# LR_EVM78.net
KiCad netlist of a schematic drawn in Altium Designer
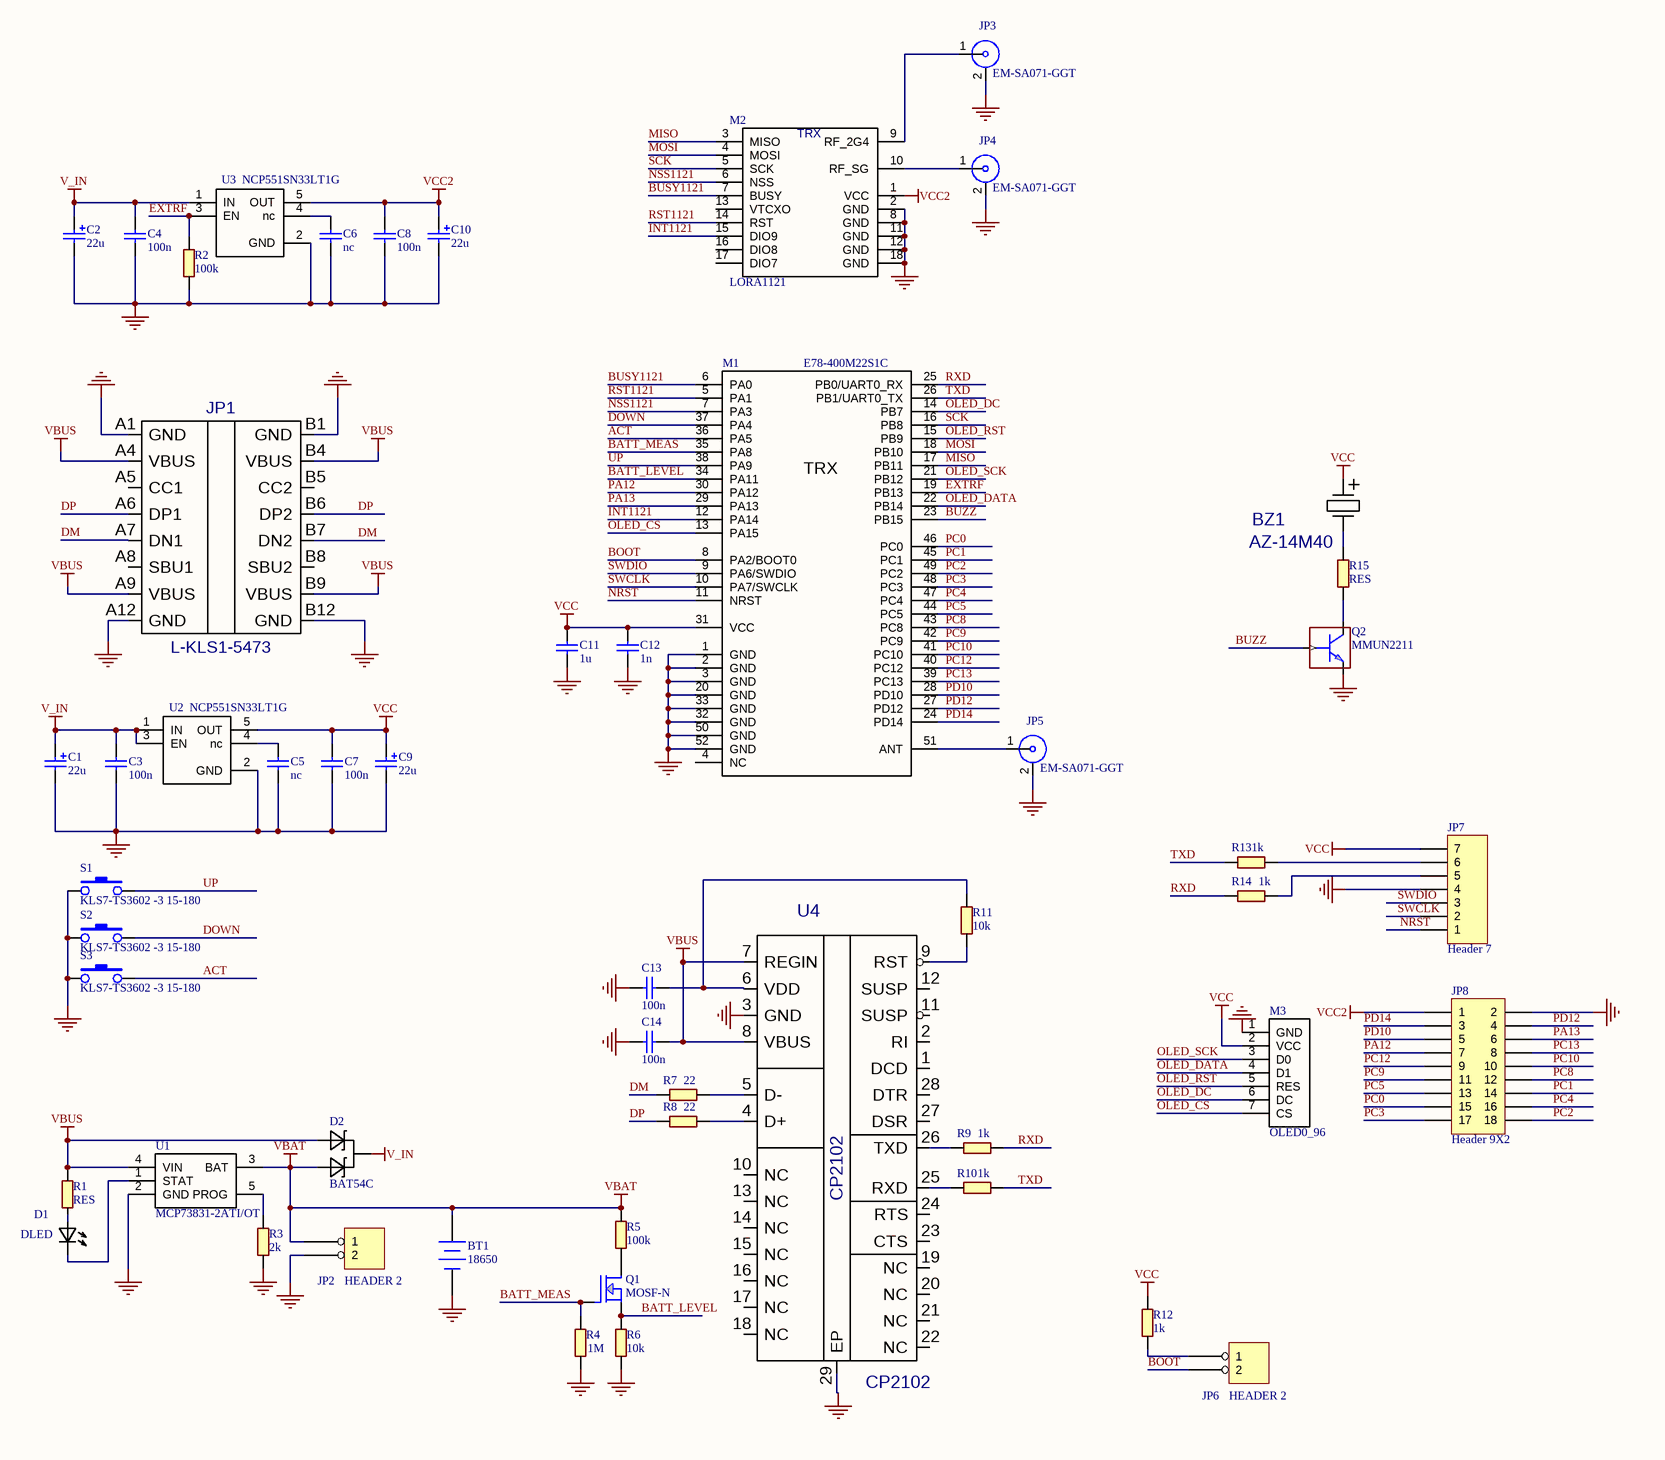
[diagram p0: LR_EVM78.SchDoc]

(export (version "E")
  (design (tool "Eeschema 10.0.6"))
  (components
    (comp (ref "BT1")
      (value "18650")
      (footprint "18650")
      (description "Multicell Battery")
      (fields (field (name "PUBLISHER") "Altium Limited"))
      (libsource (lib "zucker") (part "Battery"))
    )
    (comp (ref "BZ1")
      (value "AZ-14M40")
      (footprint "AZ-14M40")
      (libsource (lib "zucker") (part "BUZ-AZ-14M40"))
    )
    (comp (ref "C1")
      (value "22u")
      (footprint "C_TANTAL_A")
      (fields (field (name "VOLTAGE") "16V"))
      (libsource (lib "Passive") (part "CAPP"))
    )
    (comp (ref "C2")
      (value "22u")
      (footprint "C_TANTAL_A")
      (fields (field (name "VOLTAGE") "16V"))
      (libsource (lib "Passive") (part "CAPP"))
    )
    (comp (ref "C3")
      (value "100n")
      (footprint "C-0603")
      (fields (field (name "VOLTAGE") "50V"))
      (libsource (lib "Passive") (part "CAPN"))
    )
    (comp (ref "C4")
      (value "100n")
      (footprint "C-0603")
      (fields (field (name "VOLTAGE") "50V"))
      (libsource (lib "Passive") (part "CAPN"))
    )
    (comp (ref "C5")
      (value "nc")
      (footprint "C-0603")
      (fields (field (name "VOLTAGE") "50V"))
      (libsource (lib "Passive") (part "CAPN"))
    )
    (comp (ref "C6")
      (value "nc")
      (footprint "C-0603")
      (fields (field (name "VOLTAGE") "50V"))
      (libsource (lib "Passive") (part "CAPN"))
    )
    (comp (ref "C7")
      (value "100n")
      (footprint "C-0603")
      (fields (field (name "VOLTAGE") "50V"))
      (libsource (lib "Passive") (part "CAPN"))
    )
    (comp (ref "C8")
      (value "100n")
      (footprint "C-0603")
      (fields (field (name "VOLTAGE") "50V"))
      (libsource (lib "Passive") (part "CAPN"))
    )
    (comp (ref "C9")
      (value "22u")
      (footprint "C_TANTAL_A")
      (fields (field (name "VOLTAGE") "16V"))
      (libsource (lib "Passive") (part "CAPP"))
    )
    (comp (ref "C10")
      (value "22u")
      (footprint "C_TANTAL_A")
      (fields (field (name "VOLTAGE") "16V"))
      (libsource (lib "Passive") (part "CAPP"))
    )
    (comp (ref "C11")
      (value "1u")
      (footprint "C-0603")
      (fields (field (name "VOLTAGE") "50V"))
      (libsource (lib "Passive") (part "CAPN"))
    )
    (comp (ref "C12")
      (value "1n")
      (footprint "C-0603")
      (fields (field (name "VOLTAGE") "50V"))
      (libsource (lib "Passive") (part "CAPN"))
    )
    (comp (ref "C13")
      (value "100n")
      (footprint "C-0603")
      (fields (field (name "VOLTAGE") "50V"))
      (libsource (lib "Passive") (part "CAPN"))
    )
    (comp (ref "C14")
      (value "100n")
      (footprint "C-0603")
      (fields (field (name "VOLTAGE") "50V"))
      (libsource (lib "Passive") (part "CAPN"))
    )
    (comp (ref "D1") (value "DLED") (footprint "LED_3mm_RED") (libsource (lib "zucker") (part "DLED")))
    (comp (ref "D2") (value "BAT54C") (footprint "SOT-23") (libsource (lib "zucker") (part "BAT54C")))
    (comp (ref "JP1")
      (value "L-KLS1-5473")
      (footprint "L-KLS1-5473")
      (libsource (lib "connectors") (part "L-KLS1-5473"))
    )
    (comp (ref "JP2")
      (value "HEADER 2")
      (footprint "PLS1-2")
      (libsource (lib "Connectors") (part "HEADER 2"))
    )
    (comp (ref "JP3")
      (value "EM-SA071-GGT")
      (footprint "SMA_F_EDGE")
      (description "SMA Female R/A PCB Mount")
      (libsource (lib "Connectors") (part "SMA"))
    )
    (comp (ref "JP4")
      (value "EM-SA071-GGT")
      (footprint "SMA_F_EDGE")
      (description "SMA Female R/A PCB Mount")
      (libsource (lib "Connectors") (part "SMA"))
    )
    (comp (ref "JP5")
      (value "EM-SA071-GGT")
      (footprint "SMA_F_EDGE")
      (description "SMA Female R/A PCB Mount")
      (libsource (lib "Connectors") (part "SMA"))
    )
    (comp (ref "JP6")
      (value "HEADER 2")
      (footprint "PLS1-2")
      (libsource (lib "Connectors") (part "HEADER 2"))
    )
    (comp (ref "JP7")
      (value "Header 7")
      (footprint "PLS1-7R")
      (description "Header, 7-Pin")
      (fields (field (name "PUBLISHER") "Altium Limited"))
      (libsource (lib "Miscellaneous Connectors") (part "Header 7"))
    )
    (comp (ref "JP8")
      (value "Header 9X2")
      (footprint "HDR2X9")
      (description "Header, 9-Pin, Dual row")
      (fields (field (name "PUBLISHER") "Altium Limited"))
      (libsource (lib "Miscellaneous Connectors") (part "Header 9X2"))
    )
    (comp (ref "M1")
      (value "E78-400M22S1C")
      (footprint "E78_400_M22S1C")
      (libsource (lib "zucker") (part "E78-400M22S1C"))
    )
    (comp (ref "M2") (value "LORA1121") (footprint "LORA1121") (libsource (lib "zucker") (part "LORA1121")))
    (comp (ref "M3") (value "OLED0_96") (footprint "OLED096") (libsource (lib "zucker") (part "OLED0_96")))
    (comp (ref "Q1") (value "MOSF-N") (footprint "SOT-23") (libsource (lib "Transistors") (part "MOSF-N")))
    (comp (ref "Q2")
      (value "MMUN2211")
      (footprint "SOT-23")
      (libsource (lib "Transistors") (part "MMUN2211"))
    )
    (comp (ref "R1") (value "RES") (footprint "R-0603") (libsource (lib "") (part "RES_1")))
    (comp (ref "R2") (value "100k") (footprint "R-0603") (libsource (lib "") (part "RES_2")))
    (comp (ref "R3") (value "2k") (footprint "R-0603") (libsource (lib "") (part "RES_2")))
    (comp (ref "R4") (value "1M") (footprint "R-0603") (libsource (lib "") (part "RES_1")))
    (comp (ref "R5") (value "100k") (footprint "R-0603") (libsource (lib "") (part "RES_1")))
    (comp (ref "R6") (value "10k") (footprint "R-0603") (libsource (lib "") (part "RES_1")))
    (comp (ref "R7") (value "22") (footprint "R-0603") (libsource (lib "Passive") (part "RES")))
    (comp (ref "R8") (value "22") (footprint "R-0603") (libsource (lib "Passive") (part "RES")))
    (comp (ref "R9") (value "1k") (footprint "R-0603") (libsource (lib "Passive") (part "RES")))
    (comp (ref "R10") (value "1k") (footprint "R-0603") (libsource (lib "Passive") (part "RES")))
    (comp (ref "R11") (value "10k") (footprint "R-0603") (libsource (lib "") (part "RES_1")))
    (comp (ref "R12") (value "1k") (footprint "R-0603") (libsource (lib "") (part "RES_1")))
    (comp (ref "R13") (value "1k") (footprint "R-0603") (libsource (lib "Passive") (part "RES")))
    (comp (ref "R14") (value "1k") (footprint "R-0603") (libsource (lib "Passive") (part "RES")))
    (comp (ref "R15") (value "RES") (footprint "R-0603") (libsource (lib "") (part "RES_1")))
    (comp (ref "S1")
      (value "KLS7-TS3602 -3 15-180")
      (footprint "KLS7-TS3602")
      (libsource (lib "Switches") (part "SW-1"))
    )
    (comp (ref "S2")
      (value "KLS7-TS3602 -3 15-180")
      (footprint "KLS7-TS3602")
      (libsource (lib "Switches") (part "SW-1"))
    )
    (comp (ref "S3")
      (value "KLS7-TS3602 -3 15-180")
      (footprint "KLS7-TS3602")
      (libsource (lib "Switches") (part "SW-1"))
    )
    (comp (ref "U1")
      (value "MCP73831-2ATI/OT")
      (footprint "SOT-23-5")
      (libsource (lib "zucker") (part "MCP73831"))
    )
    (comp (ref "U2")
      (value "NCP551SN33LT1G")
      (footprint "SOT-23-5")
      (description "50mA Low-Dropout Regulator")
      (libsource (lib "zucker") (part "LP2980"))
    )
    (comp (ref "U3")
      (value "NCP551SN33LT1G")
      (footprint "SOT-23-5")
      (description "50mA Low-Dropout Regulator")
      (libsource (lib "zucker") (part "LP2980"))
    )
    (comp (ref "U4") (value "CP2102") (footprint "QFN28") (libsource (lib "E2002") (part "CP2102")))
  )
  (nets
    (net (code "1") (name "/ACT") (class "Default")
      (node (ref "M1") (pin "36") (pinfunction "PA5_36") (pintype "passive"))
      (node (ref "S3") (pin "2") (pinfunction "2_2") (pintype "passive"))
    )
    (net (code "2") (name "/BATT_LEVEL") (class "Default")
      (node (ref "M1") (pin "34") (pinfunction "PA11_34") (pintype "passive"))
      (node (ref "Q1") (pin "2") (pinfunction "SOURCE_2") (pintype "passive"))
      (node (ref "R6") (pin "1") (pinfunction "1_1") (pintype "passive"))
    )
    (net (code "3") (name "/BATT_MEAS") (class "Default")
      (node (ref "M1") (pin "35") (pinfunction "PA8_35") (pintype "passive"))
      (node (ref "Q1") (pin "1") (pinfunction "GATE_1") (pintype "passive"))
      (node (ref "R4") (pin "1") (pinfunction "1_1") (pintype "passive"))
    )
    (net (code "4") (name "/BOOT") (class "Default")
      (node (ref "JP6") (pin "2") (pinfunction "2_2") (pintype "passive"))
      (node (ref "M1") (pin "8") (pinfunction "PA2/BOOT0_8") (pintype "passive"))
    )
    (net (code "5") (name "/BUSY1121") (class "Default")
      (node (ref "M1") (pin "6") (pinfunction "PA0_6") (pintype "passive"))
      (node (ref "M2") (pin "7") (pinfunction "BUSY_7") (pintype "passive"))
    )
    (net (code "6") (name "/BUZZ") (class "Default")
      (node (ref "M1") (pin "23") (pinfunction "PB15_23") (pintype "passive"))
      (node (ref "Q2") (pin "1") (pinfunction "BASE_1") (pintype "input"))
    )
    (net (code "7") (name "/DM") (class "Default")
      (node (ref "JP1") (pin "A7") (pinfunction "DN1_A7") (pintype "passive"))
      (node (ref "JP1") (pin "B7") (pinfunction "DN2_B7") (pintype "passive"))
      (node (ref "R7") (pin "2") (pinfunction "2_2") (pintype "passive"))
    )
    (net (code "8") (name "/DOWN") (class "Default")
      (node (ref "M1") (pin "37") (pinfunction "PA4_37") (pintype "passive"))
      (node (ref "S2") (pin "2") (pinfunction "2_2") (pintype "passive"))
    )
    (net (code "9") (name "/DP") (class "Default")
      (node (ref "JP1") (pin "A6") (pinfunction "DP1_A6") (pintype "passive"))
      (node (ref "JP1") (pin "B6") (pinfunction "DP2_B6") (pintype "passive"))
      (node (ref "R8") (pin "2") (pinfunction "2_2") (pintype "passive"))
    )
    (net (code "10") (name "/EXTRF") (class "Default")
      (node (ref "M1") (pin "19") (pinfunction "PB13_19") (pintype "passive"))
      (node (ref "R2") (pin "2") (pinfunction "2_2") (pintype "passive"))
      (node (ref "U3") (pin "3") (pinfunction "EN_3") (pintype "passive"))
    )
    (net (code "11") (name "/INT1121") (class "Default")
      (node (ref "M1") (pin "12") (pinfunction "PA14_12") (pintype "passive"))
      (node (ref "M2") (pin "15") (pinfunction "DIO9_15") (pintype "passive"))
    )
    (net (code "12") (name "/MISO") (class "Default")
      (node (ref "M1") (pin "17") (pinfunction "PB11_17") (pintype "passive"))
      (node (ref "M2") (pin "3") (pinfunction "MISO_3") (pintype "passive"))
    )
    (net (code "13") (name "/MOSI") (class "Default")
      (node (ref "M1") (pin "18") (pinfunction "PB10_18") (pintype "passive"))
      (node (ref "M2") (pin "4") (pinfunction "MOSI_4") (pintype "passive"))
    )
    (net (code "14") (name "/NRST") (class "Default")
      (node (ref "JP7") (pin "1") (pinfunction "1_1") (pintype "passive"))
      (node (ref "M1") (pin "11") (pinfunction "NRST_11") (pintype "passive"))
    )
    (net (code "15") (name "/NSS1121") (class "Default")
      (node (ref "M1") (pin "7") (pinfunction "PA3_7") (pintype "passive"))
      (node (ref "M2") (pin "6") (pinfunction "NSS_6") (pintype "passive"))
    )
    (net (code "16") (name "/OLED_CS") (class "Default")
      (node (ref "M1") (pin "13") (pinfunction "PA15_13") (pintype "passive"))
      (node (ref "M3") (pin "7") (pinfunction "CS_7") (pintype "passive"))
    )
    (net (code "17") (name "/OLED_DATA") (class "Default")
      (node (ref "M1") (pin "22") (pinfunction "PB14_22") (pintype "passive"))
      (node (ref "M3") (pin "4") (pinfunction "D1_4") (pintype "passive"))
    )
    (net (code "18") (name "/OLED_DC") (class "Default")
      (node (ref "M1") (pin "14") (pinfunction "PB7_14") (pintype "passive"))
      (node (ref "M3") (pin "6") (pinfunction "DC_6") (pintype "passive"))
    )
    (net (code "19") (name "/OLED_RST") (class "Default")
      (node (ref "M1") (pin "15") (pinfunction "PB9_15") (pintype "passive"))
      (node (ref "M3") (pin "5") (pinfunction "RES_5") (pintype "passive"))
    )
    (net (code "20") (name "/OLED_SCK") (class "Default")
      (node (ref "M1") (pin "21") (pinfunction "PB12_21") (pintype "passive"))
      (node (ref "M3") (pin "3") (pinfunction "D0_3") (pintype "passive"))
    )
    (net (code "21") (name "/PA12") (class "Default")
      (node (ref "JP8") (pin "7") (pinfunction "7_7") (pintype "passive"))
      (node (ref "M1") (pin "30") (pinfunction "PA12_30") (pintype "passive"))
    )
    (net (code "22") (name "/PA13") (class "Default")
      (node (ref "JP8") (pin "6") (pinfunction "6_6") (pintype "passive"))
      (node (ref "M1") (pin "29") (pinfunction "PA13_29") (pintype "passive"))
    )
    (net (code "23") (name "/PC0") (class "Default")
      (node (ref "JP8") (pin "15") (pinfunction "15_15") (pintype "passive"))
      (node (ref "M1") (pin "46") (pinfunction "PC0_46") (pintype "passive"))
    )
    (net (code "24") (name "/PC1") (class "Default")
      (node (ref "JP8") (pin "14") (pinfunction "14_14") (pintype "passive"))
      (node (ref "M1") (pin "45") (pinfunction "PC1_45") (pintype "passive"))
    )
    (net (code "25") (name "/PC2") (class "Default")
      (node (ref "JP8") (pin "18") (pinfunction "18_18") (pintype "passive"))
      (node (ref "M1") (pin "49") (pinfunction "PC2_49") (pintype "passive"))
    )
    (net (code "26") (name "/PC3") (class "Default")
      (node (ref "JP8") (pin "17") (pinfunction "17_17") (pintype "passive"))
      (node (ref "M1") (pin "48") (pinfunction "PC3_48") (pintype "passive"))
    )
    (net (code "27") (name "/PC4") (class "Default")
      (node (ref "JP8") (pin "16") (pinfunction "16_16") (pintype "passive"))
      (node (ref "M1") (pin "47") (pinfunction "PC4_47") (pintype "passive"))
    )
    (net (code "28") (name "/PC5") (class "Default")
      (node (ref "JP8") (pin "13") (pinfunction "13_13") (pintype "passive"))
      (node (ref "M1") (pin "44") (pinfunction "PC5_44") (pintype "passive"))
    )
    (net (code "29") (name "/PC8") (class "Default")
      (node (ref "JP8") (pin "12") (pinfunction "12_12") (pintype "passive"))
      (node (ref "M1") (pin "43") (pinfunction "PC8_43") (pintype "passive"))
    )
    (net (code "30") (name "/PC9") (class "Default")
      (node (ref "JP8") (pin "11") (pinfunction "11_11") (pintype "passive"))
      (node (ref "M1") (pin "42") (pinfunction "PC9_42") (pintype "passive"))
    )
    (net (code "31") (name "/PC10") (class "Default")
      (node (ref "JP8") (pin "10") (pinfunction "10_10") (pintype "passive"))
      (node (ref "M1") (pin "41") (pinfunction "PC10_41") (pintype "passive"))
    )
    (net (code "32") (name "/PC12") (class "Default")
      (node (ref "JP8") (pin "9") (pinfunction "9_9") (pintype "passive"))
      (node (ref "M1") (pin "40") (pinfunction "PC12_40") (pintype "passive"))
    )
    (net (code "33") (name "/PC13") (class "Default")
      (node (ref "JP8") (pin "8") (pinfunction "8_8") (pintype "passive"))
      (node (ref "M1") (pin "39") (pinfunction "PC13_39") (pintype "passive"))
    )
    (net (code "34") (name "/PD10") (class "Default")
      (node (ref "JP8") (pin "5") (pinfunction "5_5") (pintype "passive"))
      (node (ref "M1") (pin "28") (pinfunction "PD10_28") (pintype "passive"))
    )
    (net (code "35") (name "/PD12") (class "Default")
      (node (ref "JP8") (pin "4") (pinfunction "4_4") (pintype "passive"))
      (node (ref "M1") (pin "27") (pinfunction "PD12_27") (pintype "passive"))
    )
    (net (code "36") (name "/PD14") (class "Default")
      (node (ref "JP8") (pin "3") (pinfunction "3_3") (pintype "passive"))
      (node (ref "M1") (pin "24") (pinfunction "PD14_24") (pintype "passive"))
    )
    (net (code "37") (name "/RST1121") (class "Default")
      (node (ref "M1") (pin "5") (pinfunction "PA1_5") (pintype "passive"))
      (node (ref "M2") (pin "14") (pinfunction "RST_14") (pintype "passive"))
    )
    (net (code "38") (name "/RXD") (class "Default")
      (node (ref "M1") (pin "25") (pinfunction "PB0/UART0_RX_25") (pintype "passive"))
      (node (ref "R14") (pin "2") (pinfunction "2_2") (pintype "passive"))
      (node (ref "R9") (pin "1") (pinfunction "1_1") (pintype "passive"))
    )
    (net (code "39") (name "/SCK") (class "Default")
      (node (ref "M1") (pin "16") (pinfunction "PB8_16") (pintype "passive"))
      (node (ref "M2") (pin "5") (pinfunction "SCK_5") (pintype "passive"))
    )
    (net (code "40") (name "/SWCLK") (class "Default")
      (node (ref "JP7") (pin "2") (pinfunction "2_2") (pintype "passive"))
      (node (ref "M1") (pin "10") (pinfunction "PA7/SWCLK_10") (pintype "passive"))
    )
    (net (code "41") (name "/SWDIO") (class "Default")
      (node (ref "JP7") (pin "3") (pinfunction "3_3") (pintype "passive"))
      (node (ref "M1") (pin "9") (pinfunction "PA6/SWDIO_9") (pintype "passive"))
    )
    (net (code "42") (name "/TXD") (class "Default")
      (node (ref "M1") (pin "26") (pinfunction "PB1/UART0_TX_26") (pintype "passive"))
      (node (ref "R10") (pin "1") (pinfunction "1_1") (pintype "passive"))
      (node (ref "R13") (pin "2") (pinfunction "2_2") (pintype "passive"))
    )
    (net (code "43") (name "/UP") (class "Default")
      (node (ref "M1") (pin "38") (pinfunction "PA9_38") (pintype "passive"))
      (node (ref "S1") (pin "2") (pinfunction "2_2") (pintype "passive"))
    )
    (net (code "44") (name "GND") (class "Default")
      (node (ref "BT1") (pin "2") (pinfunction "-_2") (pintype "passive"))
      (node (ref "C1") (pin "1") (pinfunction "1_1") (pintype "passive"))
      (node (ref "C10") (pin "1") (pinfunction "1_1") (pintype "passive"))
      (node (ref "C11") (pin "2") (pinfunction "2_2") (pintype "passive"))
      (node (ref "C12") (pin "2") (pinfunction "2_2") (pintype "passive"))
      (node (ref "C13") (pin "2") (pinfunction "2_2") (pintype "passive"))
      (node (ref "C14") (pin "1") (pinfunction "1_1") (pintype "passive"))
      (node (ref "C2") (pin "1") (pinfunction "1_1") (pintype "passive"))
      (node (ref "C3") (pin "2") (pinfunction "2_2") (pintype "passive"))
      (node (ref "C4") (pin "2") (pinfunction "2_2") (pintype "passive"))
      (node (ref "C5") (pin "2") (pinfunction "2_2") (pintype "passive"))
      (node (ref "C6") (pin "2") (pinfunction "2_2") (pintype "passive"))
      (node (ref "C7") (pin "2") (pinfunction "2_2") (pintype "passive"))
      (node (ref "C8") (pin "2") (pinfunction "2_2") (pintype "passive"))
      (node (ref "C9") (pin "1") (pinfunction "1_1") (pintype "passive"))
      (node (ref "JP1") (pin "A1") (pinfunction "GND_A1") (pintype "passive"))
      (node (ref "JP1") (pin "A12") (pinfunction "GND_A12") (pintype "passive"))
      (node (ref "JP1") (pin "B1") (pinfunction "GND_B1") (pintype "passive"))
      (node (ref "JP1") (pin "B12") (pinfunction "GND_B12") (pintype "passive"))
      (node (ref "JP2") (pin "2") (pinfunction "2_2") (pintype "passive"))
      (node (ref "JP3") (pin "2") (pinfunction "2_2") (pintype "passive"))
      (node (ref "JP4") (pin "2") (pinfunction "2_2") (pintype "passive"))
      (node (ref "JP5") (pin "2") (pinfunction "2_2") (pintype "passive"))
      (node (ref "JP7") (pin "4") (pinfunction "4_4") (pintype "passive"))
      (node (ref "JP8") (pin "2") (pinfunction "2_2") (pintype "passive"))
      (node (ref "M1") (pin "1") (pinfunction "GND_1") (pintype "passive"))
      (node (ref "M1") (pin "2") (pinfunction "GND_2") (pintype "passive"))
      (node (ref "M1") (pin "20") (pinfunction "GND_20") (pintype "passive"))
      (node (ref "M1") (pin "3") (pinfunction "GND_3") (pintype "passive"))
      (node (ref "M1") (pin "32") (pinfunction "GND_32") (pintype "passive"))
      (node (ref "M1") (pin "33") (pinfunction "GND_33") (pintype "passive"))
      (node (ref "M1") (pin "50") (pinfunction "GND_50") (pintype "passive"))
      (node (ref "M1") (pin "52") (pinfunction "GND_52") (pintype "passive"))
      (node (ref "M2") (pin "11") (pinfunction "GND_11") (pintype "passive"))
      (node (ref "M2") (pin "12") (pinfunction "GND_12") (pintype "passive"))
      (node (ref "M2") (pin "18") (pinfunction "GND_18") (pintype "passive"))
      (node (ref "M2") (pin "2") (pinfunction "GND_2") (pintype "passive"))
      (node (ref "M2") (pin "8") (pinfunction "GND_8") (pintype "passive"))
      (node (ref "M3") (pin "1") (pinfunction "GND_1") (pintype "passive"))
      (node (ref "Q2") (pin "2") (pinfunction "EMITTER_2") (pintype "passive"))
      (node (ref "R2") (pin "1") (pinfunction "1_1") (pintype "passive"))
      (node (ref "R3") (pin "1") (pinfunction "1_1") (pintype "passive"))
      (node (ref "R4") (pin "2") (pinfunction "2_2") (pintype "passive"))
      (node (ref "R6") (pin "2") (pinfunction "2_2") (pintype "passive"))
      (node (ref "S1") (pin "1") (pinfunction "1_1") (pintype "passive"))
      (node (ref "S2") (pin "1") (pinfunction "1_1") (pintype "passive"))
      (node (ref "S3") (pin "1") (pinfunction "1_1") (pintype "passive"))
      (node (ref "U1") (pin "2") (pinfunction "GND_2") (pintype "passive"))
      (node (ref "U2") (pin "2") (pinfunction "GND_2") (pintype "passive"))
      (node (ref "U3") (pin "2") (pinfunction "GND_2") (pintype "passive"))
      (node (ref "U4") (pin "29") (pinfunction "EP_29") (pintype "passive"))
      (node (ref "U4") (pin "3") (pinfunction "GND_3") (pintype "passive"))
    )
    (net (code "45") (name "Net-(BZ1-Pad2)") (class "Default")
      (node (ref "BZ1") (pin "2") (pinfunction "2_2") (pintype "passive"))
      (node (ref "R15") (pin "1") (pinfunction "1_1") (pintype "passive"))
    )
    (net (code "46") (name "Net-(D1-Pad1)") (class "Default")
      (node (ref "D1") (pin "1") (pinfunction "1_1") (pintype "passive"))
      (node (ref "R1") (pin "2") (pinfunction "2_2") (pintype "passive"))
    )
    (net (code "47") (name "Net-(JP6-Pad1)") (class "Default")
      (node (ref "JP6") (pin "1") (pinfunction "1_1") (pintype "passive"))
      (node (ref "R12") (pin "2") (pinfunction "2_2") (pintype "passive"))
    )
    (net (code "48") (name "Net-(JP7-Pad5)") (class "Default")
      (node (ref "JP7") (pin "5") (pinfunction "5_5") (pintype "passive"))
      (node (ref "R14") (pin "1") (pinfunction "1_1") (pintype "passive"))
    )
    (net (code "49") (name "Net-(JP7-Pad6)") (class "Default")
      (node (ref "JP7") (pin "6") (pinfunction "6_6") (pintype "passive"))
      (node (ref "R13") (pin "1") (pinfunction "1_1") (pintype "passive"))
    )
    (net (code "50") (name "Net-(M1-ANT)") (class "Default")
      (node (ref "JP5") (pin "1") (pinfunction "1_1") (pintype "passive"))
      (node (ref "M1") (pin "51") (pinfunction "ANT_51") (pintype "passive"))
    )
    (net (code "51") (name "Net-(M2-RF_2G4)") (class "Default")
      (node (ref "JP3") (pin "1") (pinfunction "1_1") (pintype "passive"))
      (node (ref "M2") (pin "9") (pinfunction "RF_2G4_9") (pintype "passive"))
    )
    (net (code "52") (name "Net-(M2-RF_SG)") (class "Default")
      (node (ref "JP4") (pin "1") (pinfunction "1_1") (pintype "passive"))
      (node (ref "M2") (pin "10") (pinfunction "RF_SG_10") (pintype "passive"))
    )
    (net (code "53") (name "Net-(Q1-DRAIN)") (class "Default")
      (node (ref "Q1") (pin "3") (pinfunction "DRAIN_3") (pintype "passive"))
      (node (ref "R5") (pin "2") (pinfunction "2_2") (pintype "passive"))
    )
    (net (code "54") (name "Net-(Q2-COLLECTOR)") (class "Default")
      (node (ref "Q2") (pin "3") (pinfunction "COLLECTOR_3") (pintype "passive"))
      (node (ref "R15") (pin "2") (pinfunction "2_2") (pintype "passive"))
    )
    (net (code "55") (name "Net-(U1-PROG)") (class "Default")
      (node (ref "R3") (pin "2") (pinfunction "2_2") (pintype "passive"))
      (node (ref "U1") (pin "5") (pinfunction "PROG_5") (pintype "passive"))
    )
    (net (code "56") (name "Net-(U1-STAT)") (class "Default")
      (node (ref "D1") (pin "2") (pinfunction "2_2") (pintype "passive"))
      (node (ref "U1") (pin "1") (pinfunction "STAT_1") (pintype "passive"))
    )
    (net (code "57") (name "Net-(U2-nc)") (class "Default")
      (node (ref "C5") (pin "1") (pinfunction "1_1") (pintype "passive"))
      (node (ref "U2") (pin "4") (pinfunction "nc_4") (pintype "passive"))
    )
    (net (code "58") (name "Net-(U3-nc)") (class "Default")
      (node (ref "C6") (pin "1") (pinfunction "1_1") (pintype "passive"))
      (node (ref "U3") (pin "4") (pinfunction "nc_4") (pintype "passive"))
    )
    (net (code "59") (name "Net-(U4-D+)") (class "Default")
      (node (ref "R8") (pin "1") (pinfunction "1_1") (pintype "passive"))
      (node (ref "U4") (pin "4") (pinfunction "D+_4") (pintype "passive"))
    )
    (net (code "60") (name "Net-(U4-D-)") (class "Default")
      (node (ref "R7") (pin "1") (pinfunction "1_1") (pintype "passive"))
      (node (ref "U4") (pin "5") (pinfunction "D-_5") (pintype "passive"))
    )
    (net (code "61") (name "Net-(U4-RST)") (class "Default")
      (node (ref "R11") (pin "2") (pinfunction "2_2") (pintype "passive"))
      (node (ref "U4") (pin "9") (pinfunction "RST_9") (pintype "passive"))
    )
    (net (code "62") (name "Net-(U4-RXD)") (class "Default")
      (node (ref "R10") (pin "2") (pinfunction "2_2") (pintype "passive"))
      (node (ref "U4") (pin "25") (pinfunction "RXD_25") (pintype "passive"))
    )
    (net (code "63") (name "Net-(U4-TXD)") (class "Default")
      (node (ref "R9") (pin "2") (pinfunction "2_2") (pintype "passive"))
      (node (ref "U4") (pin "26") (pinfunction "TXD_26") (pintype "passive"))
    )
    (net (code "64") (name "Net-(U4-VDD)") (class "Default")
      (node (ref "C13") (pin "1") (pinfunction "1_1") (pintype "passive"))
      (node (ref "R11") (pin "1") (pinfunction "1_1") (pintype "passive"))
      (node (ref "U4") (pin "6") (pinfunction "VDD_6") (pintype "passive"))
    )
    (net (code "65") (name "VBAT") (class "Default")
      (node (ref "BT1") (pin "1") (pinfunction "+_1") (pintype "passive"))
      (node (ref "D2") (pin "1") (pinfunction "A1_1") (pintype "passive"))
      (node (ref "JP2") (pin "1") (pinfunction "1_1") (pintype "passive"))
      (node (ref "R5") (pin "1") (pinfunction "1_1") (pintype "passive"))
      (node (ref "U1") (pin "3") (pinfunction "BAT_3") (pintype "passive"))
    )
    (net (code "66") (name "VBUS") (class "Default")
      (node (ref "C14") (pin "2") (pinfunction "2_2") (pintype "passive"))
      (node (ref "D2") (pin "2") (pinfunction "A2_2") (pintype "passive"))
      (node (ref "JP1") (pin "A4") (pinfunction "VBUS_A4") (pintype "passive"))
      (node (ref "JP1") (pin "A9") (pinfunction "VBUS_A9") (pintype "passive"))
      (node (ref "JP1") (pin "B4") (pinfunction "VBUS_B4") (pintype "passive"))
      (node (ref "JP1") (pin "B9") (pinfunction "VBUS_B9") (pintype "passive"))
      (node (ref "R1") (pin "1") (pinfunction "1_1") (pintype "passive"))
      (node (ref "U1") (pin "4") (pinfunction "VIN_4") (pintype "passive"))
      (node (ref "U4") (pin "7") (pinfunction "REGIN_7") (pintype "passive"))
      (node (ref "U4") (pin "8") (pinfunction "VBUS_8") (pintype "passive"))
    )
    (net (code "67") (name "VCC") (class "Default")
      (node (ref "BZ1") (pin "1") (pinfunction "1_1") (pintype "passive"))
      (node (ref "C11") (pin "1") (pinfunction "1_1") (pintype "passive"))
      (node (ref "C12") (pin "1") (pinfunction "1_1") (pintype "passive"))
      (node (ref "C7") (pin "1") (pinfunction "1_1") (pintype "passive"))
      (node (ref "C9") (pin "2") (pinfunction "2_2") (pintype "passive"))
      (node (ref "JP7") (pin "7") (pinfunction "7_7") (pintype "passive"))
      (node (ref "M1") (pin "31") (pinfunction "VCC_31") (pintype "passive"))
      (node (ref "M3") (pin "2") (pinfunction "VCC_2") (pintype "passive"))
      (node (ref "R12") (pin "1") (pinfunction "1_1") (pintype "passive"))
      (node (ref "U2") (pin "5") (pinfunction "OUT_5") (pintype "passive"))
    )
    (net (code "68") (name "VCC2") (class "Default")
      (node (ref "C10") (pin "2") (pinfunction "2_2") (pintype "passive"))
      (node (ref "C8") (pin "1") (pinfunction "1_1") (pintype "passive"))
      (node (ref "JP8") (pin "1") (pinfunction "1_1") (pintype "passive"))
      (node (ref "M2") (pin "1") (pinfunction "VCC_1") (pintype "passive"))
      (node (ref "U3") (pin "5") (pinfunction "OUT_5") (pintype "passive"))
    )
    (net (code "69") (name "VSS") (class "Default")
      (node (ref "JP1") (pin "17") (pinfunction "VSS_17") (pintype "power_in"))
    )
    (net (code "70") (name "V_IN") (class "Default")
      (node (ref "C1") (pin "2") (pinfunction "2_2") (pintype "passive"))
      (node (ref "C2") (pin "2") (pinfunction "2_2") (pintype "passive"))
      (node (ref "C3") (pin "1") (pinfunction "1_1") (pintype "passive"))
      (node (ref "C4") (pin "1") (pinfunction "1_1") (pintype "passive"))
      (node (ref "D2") (pin "3") (pinfunction "C1C2_3") (pintype "passive"))
      (node (ref "U2") (pin "1") (pinfunction "IN_1") (pintype "passive"))
      (node (ref "U2") (pin "3") (pinfunction "EN_3") (pintype "passive"))
      (node (ref "U3") (pin "1") (pinfunction "IN_1") (pintype "passive"))
    )
    (net (code "71") (name "unconnected-(JP1-CC1-PadA5)") (class "Default")
      (node (ref "JP1") (pin "A5") (pinfunction "CC1_A5") (pintype "passive"))
    )
    (net (code "72") (name "unconnected-(JP1-CC2-PadB5)") (class "Default")
      (node (ref "JP1") (pin "B5") (pinfunction "CC2_B5") (pintype "passive"))
    )
    (net (code "73") (name "unconnected-(JP1-SBU1-PadA8)") (class "Default")
      (node (ref "JP1") (pin "A8") (pinfunction "SBU1_A8") (pintype "passive"))
    )
    (net (code "74") (name "unconnected-(JP1-SBU2-PadB8)") (class "Default")
      (node (ref "JP1") (pin "B8") (pinfunction "SBU2_B8") (pintype "passive"))
    )
    (net (code "75") (name "unconnected-(M1-NC-Pad4)") (class "Default")
      (node (ref "M1") (pin "4") (pinfunction "NC_4") (pintype "passive"))
    )
    (net (code "76") (name "unconnected-(M2-DIO7-Pad17)") (class "Default")
      (node (ref "M2") (pin "17") (pinfunction "DIO7_17") (pintype "passive"))
    )
    (net (code "77") (name "unconnected-(M2-DIO8-Pad16)") (class "Default")
      (node (ref "M2") (pin "16") (pinfunction "DIO8_16") (pintype "passive"))
    )
    (net (code "78") (name "unconnected-(M2-VTCXO-Pad13)") (class "Default")
      (node (ref "M2") (pin "13") (pinfunction "VTCXO_13") (pintype "passive"))
    )
    (net (code "79") (name "unconnected-(U4-CTS-Pad23)") (class "Default")
      (node (ref "U4") (pin "23") (pinfunction "CTS_23") (pintype "passive"))
    )
    (net (code "80") (name "unconnected-(U4-DCD-Pad1)") (class "Default")
      (node (ref "U4") (pin "1") (pinfunction "DCD_1") (pintype "passive"))
    )
    (net (code "81") (name "unconnected-(U4-DSR-Pad27)") (class "Default")
      (node (ref "U4") (pin "27") (pinfunction "DSR_27") (pintype "passive"))
    )
    (net (code "82") (name "unconnected-(U4-DTR-Pad28)") (class "Default")
      (node (ref "U4") (pin "28") (pinfunction "DTR_28") (pintype "passive"))
    )
    (net (code "83") (name "unconnected-(U4-NC-Pad10)") (class "Default")
      (node (ref "U4") (pin "10") (pinfunction "NC_10") (pintype "passive"))
    )
    (net (code "84") (name "unconnected-(U4-NC-Pad13)") (class "Default")
      (node (ref "U4") (pin "13") (pinfunction "NC_13") (pintype "passive"))
    )
    (net (code "85") (name "unconnected-(U4-NC-Pad14)") (class "Default")
      (node (ref "U4") (pin "14") (pinfunction "NC_14") (pintype "passive"))
    )
    (net (code "86") (name "unconnected-(U4-NC-Pad15)") (class "Default")
      (node (ref "U4") (pin "15") (pinfunction "NC_15") (pintype "passive"))
    )
    (net (code "87") (name "unconnected-(U4-NC-Pad16)") (class "Default")
      (node (ref "U4") (pin "16") (pinfunction "NC_16") (pintype "passive"))
    )
    (net (code "88") (name "unconnected-(U4-NC-Pad17)") (class "Default")
      (node (ref "U4") (pin "17") (pinfunction "NC_17") (pintype "passive"))
    )
    (net (code "89") (name "unconnected-(U4-NC-Pad18)") (class "Default")
      (node (ref "U4") (pin "18") (pinfunction "NC_18") (pintype "passive"))
    )
    (net (code "90") (name "unconnected-(U4-NC-Pad19)") (class "Default")
      (node (ref "U4") (pin "19") (pinfunction "NC_19") (pintype "passive"))
    )
    (net (code "91") (name "unconnected-(U4-NC-Pad20)") (class "Default")
      (node (ref "U4") (pin "20") (pinfunction "NC_20") (pintype "passive"))
    )
    (net (code "92") (name "unconnected-(U4-NC-Pad21)") (class "Default")
      (node (ref "U4") (pin "21") (pinfunction "NC_21") (pintype "passive"))
    )
    (net (code "93") (name "unconnected-(U4-NC-Pad22)") (class "Default")
      (node (ref "U4") (pin "22") (pinfunction "NC_22") (pintype "passive"))
    )
    (net (code "94") (name "unconnected-(U4-RI-Pad2)") (class "Default")
      (node (ref "U4") (pin "2") (pinfunction "RI_2") (pintype "passive"))
    )
    (net (code "95") (name "unconnected-(U4-RTS-Pad24)") (class "Default")
      (node (ref "U4") (pin "24") (pinfunction "RTS_24") (pintype "passive"))
    )
    (net (code "96") (name "unconnected-(U4-SUSP-Pad11)") (class "Default")
      (node (ref "U4") (pin "11") (pinfunction "SUSP_11") (pintype "passive"))
    )
    (net (code "97") (name "unconnected-(U4-SUSP-Pad12)") (class "Default")
      (node (ref "U4") (pin "12") (pinfunction "SUSP_12") (pintype "passive"))
    )
  )
)
